# Sensor_LinearCCD_Socket.net
KiCad netlist of a schematic drawn in EAGLE
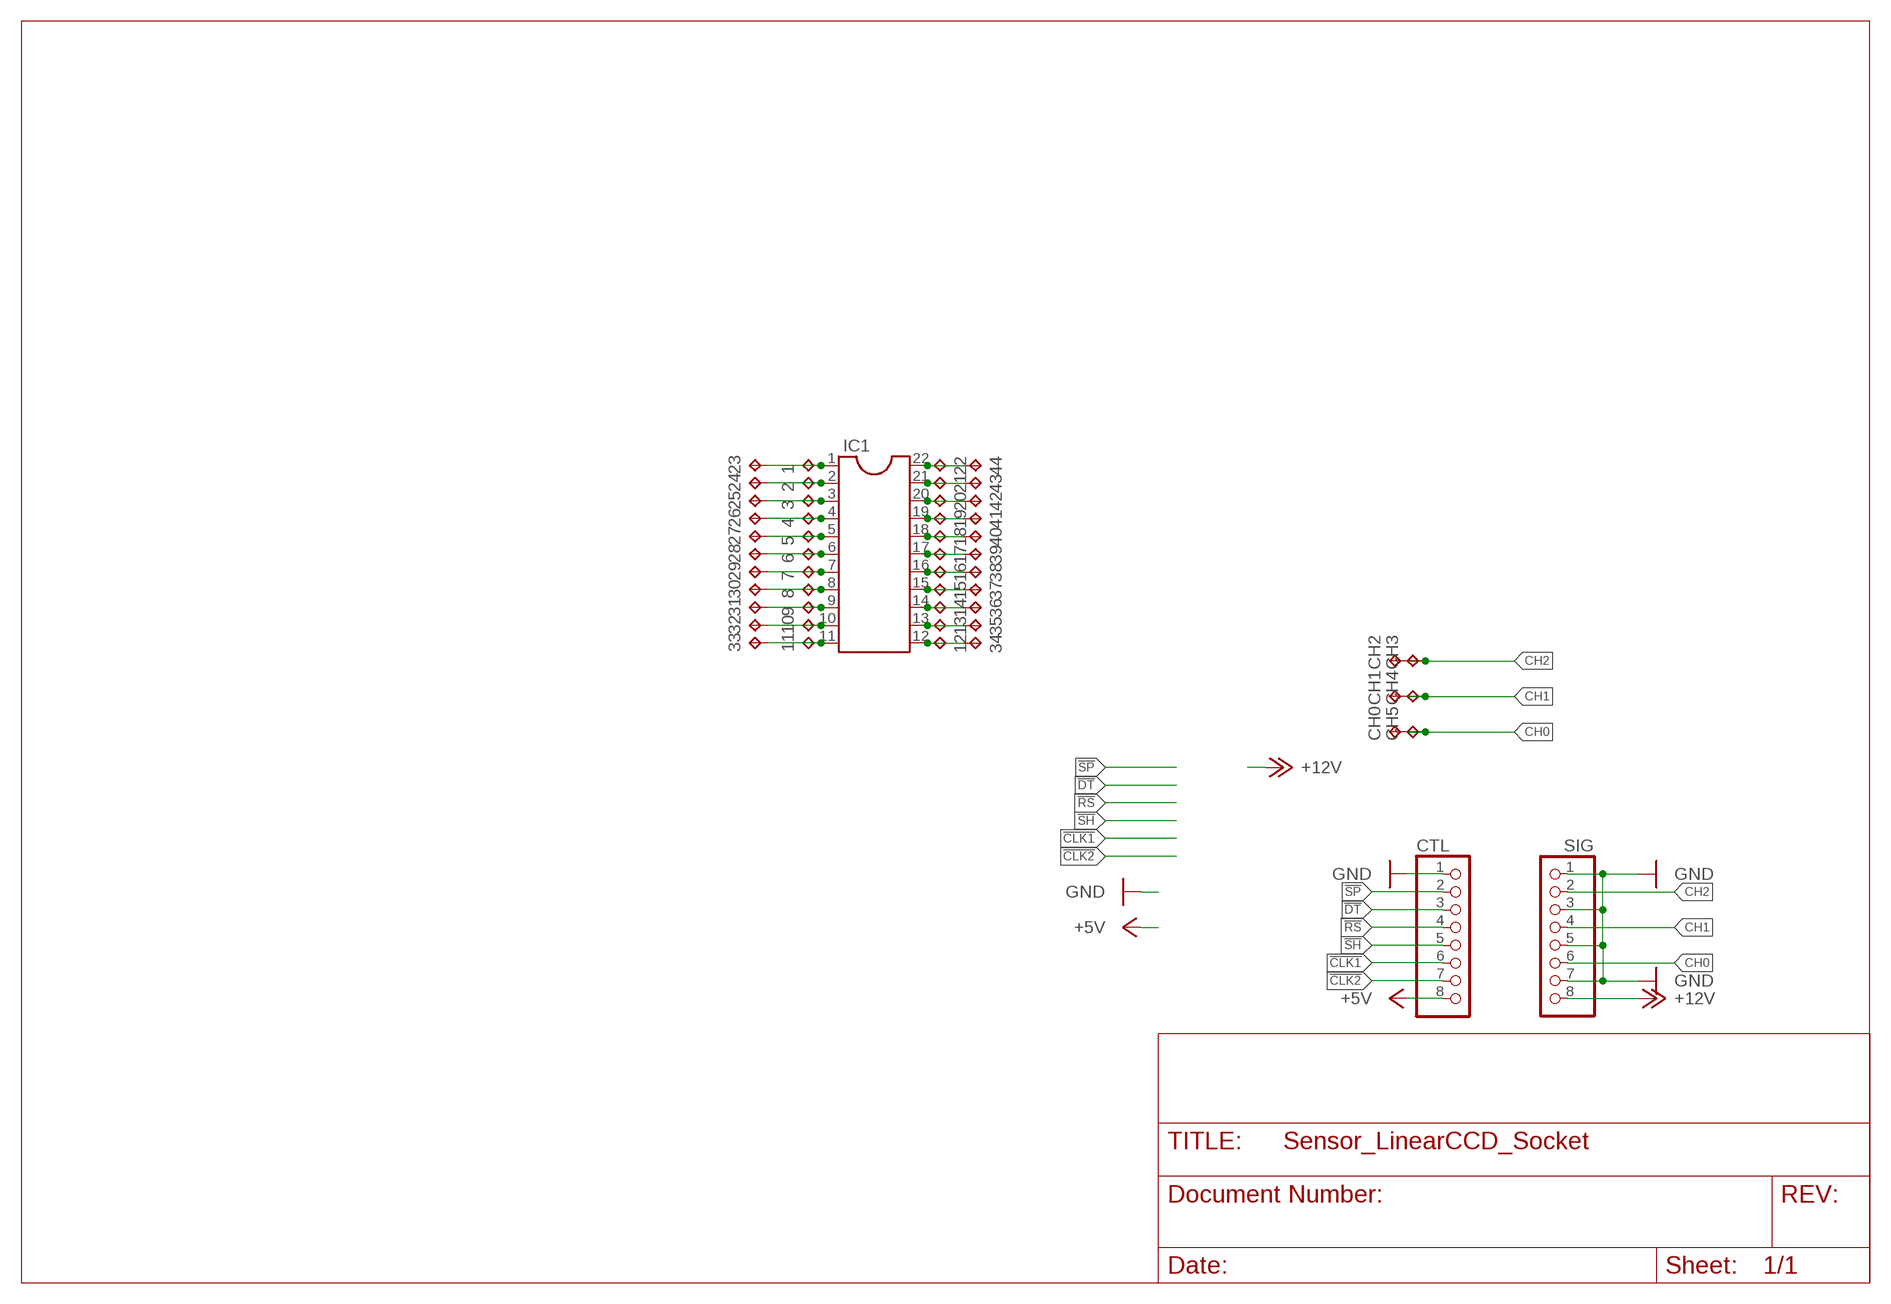
[diagram p0: schematic, sheet 1]

(export (version "E")
  (design (tool "Eeschema 10.0.6"))
  (components
    (comp (ref "1")
      (value "TPTP15SQ")
      (footprint "eagle-import:TP15SQ")
      (libsource (lib "eagle-import") (part "TPTP15SQ"))
    )
    (comp (ref "2")
      (value "TPTP15SQ")
      (footprint "eagle-import:TP15SQ")
      (libsource (lib "eagle-import") (part "TPTP15SQ"))
    )
    (comp (ref "3")
      (value "TPTP15SQ")
      (footprint "eagle-import:TP15SQ")
      (libsource (lib "eagle-import") (part "TPTP15SQ"))
    )
    (comp (ref "4")
      (value "TPTP15SQ")
      (footprint "eagle-import:TP15SQ")
      (libsource (lib "eagle-import") (part "TPTP15SQ"))
    )
    (comp (ref "5")
      (value "TPTP15SQ")
      (footprint "eagle-import:TP15SQ")
      (libsource (lib "eagle-import") (part "TPTP15SQ"))
    )
    (comp (ref "6")
      (value "TPTP15SQ")
      (footprint "eagle-import:TP15SQ")
      (libsource (lib "eagle-import") (part "TPTP15SQ"))
    )
    (comp (ref "7")
      (value "TPTP15SQ")
      (footprint "eagle-import:TP15SQ")
      (libsource (lib "eagle-import") (part "TPTP15SQ"))
    )
    (comp (ref "8")
      (value "TPTP15SQ")
      (footprint "eagle-import:TP15SQ")
      (libsource (lib "eagle-import") (part "TPTP15SQ"))
    )
    (comp (ref "9")
      (value "TPTP15SQ")
      (footprint "eagle-import:TP15SQ")
      (libsource (lib "eagle-import") (part "TPTP15SQ"))
    )
    (comp (ref "10")
      (value "TPTP15SQ")
      (footprint "eagle-import:TP15SQ")
      (libsource (lib "eagle-import") (part "TPTP15SQ"))
    )
    (comp (ref "11")
      (value "TPTP15SQ")
      (footprint "eagle-import:TP15SQ")
      (libsource (lib "eagle-import") (part "TPTP15SQ"))
    )
    (comp (ref "12")
      (value "TPTP15SQ")
      (footprint "eagle-import:TP15SQ")
      (libsource (lib "eagle-import") (part "TPTP15SQ"))
    )
    (comp (ref "13")
      (value "TPTP15SQ")
      (footprint "eagle-import:TP15SQ")
      (libsource (lib "eagle-import") (part "TPTP15SQ"))
    )
    (comp (ref "14")
      (value "TPTP15SQ")
      (footprint "eagle-import:TP15SQ")
      (libsource (lib "eagle-import") (part "TPTP15SQ"))
    )
    (comp (ref "15")
      (value "TPTP15SQ")
      (footprint "eagle-import:TP15SQ")
      (libsource (lib "eagle-import") (part "TPTP15SQ"))
    )
    (comp (ref "16")
      (value "TPTP15SQ")
      (footprint "eagle-import:TP15SQ")
      (libsource (lib "eagle-import") (part "TPTP15SQ"))
    )
    (comp (ref "17")
      (value "TPTP15SQ")
      (footprint "eagle-import:TP15SQ")
      (libsource (lib "eagle-import") (part "TPTP15SQ"))
    )
    (comp (ref "18")
      (value "TPTP15SQ")
      (footprint "eagle-import:TP15SQ")
      (libsource (lib "eagle-import") (part "TPTP15SQ"))
    )
    (comp (ref "19")
      (value "TPTP15SQ")
      (footprint "eagle-import:TP15SQ")
      (libsource (lib "eagle-import") (part "TPTP15SQ"))
    )
    (comp (ref "20")
      (value "TPTP15SQ")
      (footprint "eagle-import:TP15SQ")
      (libsource (lib "eagle-import") (part "TPTP15SQ"))
    )
    (comp (ref "21")
      (value "TPTP15SQ")
      (footprint "eagle-import:TP15SQ")
      (libsource (lib "eagle-import") (part "TPTP15SQ"))
    )
    (comp (ref "22")
      (value "TPTP15SQ")
      (footprint "eagle-import:TP15SQ")
      (libsource (lib "eagle-import") (part "TPTP15SQ"))
    )
    (comp (ref "23")
      (value "TPTP15SQ")
      (footprint "eagle-import:TP15SQ")
      (libsource (lib "eagle-import") (part "TPTP15SQ"))
    )
    (comp (ref "24")
      (value "TPTP15SQ")
      (footprint "eagle-import:TP15SQ")
      (libsource (lib "eagle-import") (part "TPTP15SQ"))
    )
    (comp (ref "25")
      (value "TPTP15SQ")
      (footprint "eagle-import:TP15SQ")
      (libsource (lib "eagle-import") (part "TPTP15SQ"))
    )
    (comp (ref "26")
      (value "TPTP15SQ")
      (footprint "eagle-import:TP15SQ")
      (libsource (lib "eagle-import") (part "TPTP15SQ"))
    )
    (comp (ref "27")
      (value "TPTP15SQ")
      (footprint "eagle-import:TP15SQ")
      (libsource (lib "eagle-import") (part "TPTP15SQ"))
    )
    (comp (ref "28")
      (value "TPTP15SQ")
      (footprint "eagle-import:TP15SQ")
      (libsource (lib "eagle-import") (part "TPTP15SQ"))
    )
    (comp (ref "29")
      (value "TPTP15SQ")
      (footprint "eagle-import:TP15SQ")
      (libsource (lib "eagle-import") (part "TPTP15SQ"))
    )
    (comp (ref "30")
      (value "TPTP15SQ")
      (footprint "eagle-import:TP15SQ")
      (libsource (lib "eagle-import") (part "TPTP15SQ"))
    )
    (comp (ref "31")
      (value "TPTP15SQ")
      (footprint "eagle-import:TP15SQ")
      (libsource (lib "eagle-import") (part "TPTP15SQ"))
    )
    (comp (ref "32")
      (value "TPTP15SQ")
      (footprint "eagle-import:TP15SQ")
      (libsource (lib "eagle-import") (part "TPTP15SQ"))
    )
    (comp (ref "33")
      (value "TPTP15SQ")
      (footprint "eagle-import:TP15SQ")
      (libsource (lib "eagle-import") (part "TPTP15SQ"))
    )
    (comp (ref "34")
      (value "TPTP15SQ")
      (footprint "eagle-import:TP15SQ")
      (libsource (lib "eagle-import") (part "TPTP15SQ"))
    )
    (comp (ref "35")
      (value "TPTP15SQ")
      (footprint "eagle-import:TP15SQ")
      (libsource (lib "eagle-import") (part "TPTP15SQ"))
    )
    (comp (ref "36")
      (value "TPTP15SQ")
      (footprint "eagle-import:TP15SQ")
      (libsource (lib "eagle-import") (part "TPTP15SQ"))
    )
    (comp (ref "37")
      (value "TPTP15SQ")
      (footprint "eagle-import:TP15SQ")
      (libsource (lib "eagle-import") (part "TPTP15SQ"))
    )
    (comp (ref "38")
      (value "TPTP15SQ")
      (footprint "eagle-import:TP15SQ")
      (libsource (lib "eagle-import") (part "TPTP15SQ"))
    )
    (comp (ref "39")
      (value "TPTP15SQ")
      (footprint "eagle-import:TP15SQ")
      (libsource (lib "eagle-import") (part "TPTP15SQ"))
    )
    (comp (ref "40")
      (value "TPTP15SQ")
      (footprint "eagle-import:TP15SQ")
      (libsource (lib "eagle-import") (part "TPTP15SQ"))
    )
    (comp (ref "41")
      (value "TPTP15SQ")
      (footprint "eagle-import:TP15SQ")
      (libsource (lib "eagle-import") (part "TPTP15SQ"))
    )
    (comp (ref "42")
      (value "TPTP15SQ")
      (footprint "eagle-import:TP15SQ")
      (libsource (lib "eagle-import") (part "TPTP15SQ"))
    )
    (comp (ref "43")
      (value "TPTP15SQ")
      (footprint "eagle-import:TP15SQ")
      (libsource (lib "eagle-import") (part "TPTP15SQ"))
    )
    (comp (ref "44")
      (value "TPTP15SQ")
      (footprint "eagle-import:TP15SQ")
      (libsource (lib "eagle-import") (part "TPTP15SQ"))
    )
    (comp (ref "CH0")
      (value "TPTP15SQ")
      (footprint "eagle-import:TP15SQ")
      (libsource (lib "eagle-import") (part "TPTP15SQ"))
    )
    (comp (ref "CH1")
      (value "TPTP15SQ")
      (footprint "eagle-import:TP15SQ")
      (libsource (lib "eagle-import") (part "TPTP15SQ"))
    )
    (comp (ref "CH2")
      (value "TPTP15SQ")
      (footprint "eagle-import:TP15SQ")
      (libsource (lib "eagle-import") (part "TPTP15SQ"))
    )
    (comp (ref "CH3")
      (value "TPTP15SQ")
      (footprint "eagle-import:TP15SQ")
      (libsource (lib "eagle-import") (part "TPTP15SQ"))
    )
    (comp (ref "CH4")
      (value "TPTP15SQ")
      (footprint "eagle-import:TP15SQ")
      (libsource (lib "eagle-import") (part "TPTP15SQ"))
    )
    (comp (ref "CH5")
      (value "TPTP15SQ")
      (footprint "eagle-import:TP15SQ")
      (libsource (lib "eagle-import") (part "TPTP15SQ"))
    )
    (comp (ref "CTL")
      (value "PINHD-1X8_2.00")
      (footprint "eagle-import:1X08M")
      (libsource (lib "eagle-import") (part "PINHD-1X8_2.00"))
    )
    (comp (ref "IC1")
      (value "DIL22-4")
      (footprint "eagle-import:DIL22-4")
      (libsource (lib "eagle-import") (part "DIL22-4"))
    )
    (comp (ref "SIG")
      (value "PINHD-1X8_2.00")
      (footprint "eagle-import:1X08M")
      (libsource (lib "eagle-import") (part "PINHD-1X8_2.00"))
    )
  )
  (nets
    (net (code "1") (name "+5V") (class "Default")
      (node (ref "CTL") (pin "8") (pinfunction "8_8") (pintype "passive"))
    )
    (net (code "2") (name "+12V") (class "Default")
      (node (ref "SIG") (pin "8") (pinfunction "8_8") (pintype "passive"))
    )
    (net (code "3") (name "/~{CLK1}") (class "Default")
      (node (ref "CTL") (pin "6") (pinfunction "6_6") (pintype "passive"))
    )
    (net (code "4") (name "/~{CLK2}") (class "Default")
      (node (ref "CTL") (pin "7") (pinfunction "7_7") (pintype "passive"))
    )
    (net (code "5") (name "/~{DT}") (class "Default")
      (node (ref "CTL") (pin "3") (pinfunction "3_3") (pintype "passive"))
    )
    (net (code "6") (name "/~{RS}") (class "Default")
      (node (ref "CTL") (pin "4") (pinfunction "4_4") (pintype "passive"))
    )
    (net (code "7") (name "/~{SH}") (class "Default")
      (node (ref "CTL") (pin "5") (pinfunction "5_5") (pintype "passive"))
    )
    (net (code "8") (name "/~{SP}") (class "Default")
      (node (ref "CTL") (pin "2") (pinfunction "2_2") (pintype "passive"))
    )
    (net (code "9") (name "CH0") (class "Default")
      (node (ref "CH0") (pin "TP") (pinfunction "TP_TP") (pintype "input"))
      (node (ref "CH5") (pin "TP") (pinfunction "TP_TP") (pintype "input"))
      (node (ref "SIG") (pin "6") (pinfunction "6_6") (pintype "passive"))
    )
    (net (code "10") (name "CH1") (class "Default")
      (node (ref "CH1") (pin "TP") (pinfunction "TP_TP") (pintype "input"))
      (node (ref "CH4") (pin "TP") (pinfunction "TP_TP") (pintype "input"))
      (node (ref "SIG") (pin "4") (pinfunction "4_4") (pintype "passive"))
    )
    (net (code "11") (name "CH2") (class "Default")
      (node (ref "CH2") (pin "TP") (pinfunction "TP_TP") (pintype "input"))
      (node (ref "CH3") (pin "TP") (pinfunction "TP_TP") (pintype "input"))
      (node (ref "SIG") (pin "2") (pinfunction "2_2") (pintype "passive"))
    )
    (net (code "12") (name "GND") (class "Default")
      (node (ref "CTL") (pin "1") (pinfunction "1_1") (pintype "passive"))
      (node (ref "SIG") (pin "1") (pinfunction "1_1") (pintype "passive"))
      (node (ref "SIG") (pin "3") (pinfunction "3_3") (pintype "passive"))
      (node (ref "SIG") (pin "5") (pinfunction "5_5") (pintype "passive"))
      (node (ref "SIG") (pin "7") (pinfunction "7_7") (pintype "passive"))
    )
    (net (code "13") (name "Net-(1-PadTP)") (class "Default")
      (node (ref "1") (pin "TP") (pinfunction "TP_TP") (pintype "input"))
      (node (ref "23") (pin "TP") (pinfunction "TP_TP") (pintype "input"))
      (node (ref "IC1") (pin "1") (pinfunction "1_1") (pintype "passive"))
    )
    (net (code "14") (name "Net-(2-PadTP)") (class "Default")
      (node (ref "2") (pin "TP") (pinfunction "TP_TP") (pintype "input"))
      (node (ref "24") (pin "TP") (pinfunction "TP_TP") (pintype "input"))
      (node (ref "IC1") (pin "2") (pinfunction "2_2") (pintype "passive"))
    )
    (net (code "15") (name "Net-(10-PadTP)") (class "Default")
      (node (ref "10") (pin "TP") (pinfunction "TP_TP") (pintype "input"))
      (node (ref "32") (pin "TP") (pinfunction "TP_TP") (pintype "input"))
      (node (ref "IC1") (pin "10") (pinfunction "10_10") (pintype "passive"))
    )
    (net (code "16") (name "Net-(11-PadTP)") (class "Default")
      (node (ref "11") (pin "TP") (pinfunction "TP_TP") (pintype "input"))
      (node (ref "33") (pin "TP") (pinfunction "TP_TP") (pintype "input"))
      (node (ref "IC1") (pin "11") (pinfunction "11_11") (pintype "passive"))
    )
    (net (code "17") (name "Net-(12-PadTP)") (class "Default")
      (node (ref "12") (pin "TP") (pinfunction "TP_TP") (pintype "input"))
      (node (ref "34") (pin "TP") (pinfunction "TP_TP") (pintype "input"))
      (node (ref "IC1") (pin "12") (pinfunction "12_12") (pintype "passive"))
    )
    (net (code "18") (name "Net-(13-PadTP)") (class "Default")
      (node (ref "13") (pin "TP") (pinfunction "TP_TP") (pintype "input"))
      (node (ref "35") (pin "TP") (pinfunction "TP_TP") (pintype "input"))
      (node (ref "IC1") (pin "13") (pinfunction "13_13") (pintype "passive"))
    )
    (net (code "19") (name "Net-(14-PadTP)") (class "Default")
      (node (ref "14") (pin "TP") (pinfunction "TP_TP") (pintype "input"))
      (node (ref "36") (pin "TP") (pinfunction "TP_TP") (pintype "input"))
      (node (ref "IC1") (pin "14") (pinfunction "14_14") (pintype "passive"))
    )
    (net (code "20") (name "Net-(15-PadTP)") (class "Default")
      (node (ref "15") (pin "TP") (pinfunction "TP_TP") (pintype "input"))
      (node (ref "37") (pin "TP") (pinfunction "TP_TP") (pintype "input"))
      (node (ref "IC1") (pin "15") (pinfunction "15_15") (pintype "passive"))
    )
    (net (code "21") (name "Net-(16-PadTP)") (class "Default")
      (node (ref "16") (pin "TP") (pinfunction "TP_TP") (pintype "input"))
      (node (ref "38") (pin "TP") (pinfunction "TP_TP") (pintype "input"))
      (node (ref "IC1") (pin "16") (pinfunction "16_16") (pintype "passive"))
    )
    (net (code "22") (name "Net-(17-PadTP)") (class "Default")
      (node (ref "17") (pin "TP") (pinfunction "TP_TP") (pintype "input"))
      (node (ref "39") (pin "TP") (pinfunction "TP_TP") (pintype "input"))
      (node (ref "IC1") (pin "17") (pinfunction "17_17") (pintype "passive"))
    )
    (net (code "23") (name "Net-(18-PadTP)") (class "Default")
      (node (ref "18") (pin "TP") (pinfunction "TP_TP") (pintype "input"))
      (node (ref "40") (pin "TP") (pinfunction "TP_TP") (pintype "input"))
      (node (ref "IC1") (pin "18") (pinfunction "18_18") (pintype "passive"))
    )
    (net (code "24") (name "Net-(19-PadTP)") (class "Default")
      (node (ref "19") (pin "TP") (pinfunction "TP_TP") (pintype "input"))
      (node (ref "41") (pin "TP") (pinfunction "TP_TP") (pintype "input"))
      (node (ref "IC1") (pin "19") (pinfunction "19_19") (pintype "passive"))
    )
    (net (code "25") (name "Net-(20-PadTP)") (class "Default")
      (node (ref "20") (pin "TP") (pinfunction "TP_TP") (pintype "input"))
      (node (ref "42") (pin "TP") (pinfunction "TP_TP") (pintype "input"))
      (node (ref "IC1") (pin "20") (pinfunction "20_20") (pintype "passive"))
    )
    (net (code "26") (name "Net-(21-PadTP)") (class "Default")
      (node (ref "21") (pin "TP") (pinfunction "TP_TP") (pintype "input"))
      (node (ref "43") (pin "TP") (pinfunction "TP_TP") (pintype "input"))
      (node (ref "IC1") (pin "21") (pinfunction "21_21") (pintype "passive"))
    )
    (net (code "27") (name "Net-(22-PadTP)") (class "Default")
      (node (ref "22") (pin "TP") (pinfunction "TP_TP") (pintype "input"))
      (node (ref "44") (pin "TP") (pinfunction "TP_TP") (pintype "input"))
      (node (ref "IC1") (pin "22") (pinfunction "22_22") (pintype "passive"))
    )
    (net (code "28") (name "Net-(25-PadTP)") (class "Default")
      (node (ref "25") (pin "TP") (pinfunction "TP_TP") (pintype "input"))
      (node (ref "3") (pin "TP") (pinfunction "TP_TP") (pintype "input"))
      (node (ref "IC1") (pin "3") (pinfunction "3_3") (pintype "passive"))
    )
    (net (code "29") (name "Net-(26-PadTP)") (class "Default")
      (node (ref "26") (pin "TP") (pinfunction "TP_TP") (pintype "input"))
      (node (ref "4") (pin "TP") (pinfunction "TP_TP") (pintype "input"))
      (node (ref "IC1") (pin "4") (pinfunction "4_4") (pintype "passive"))
    )
    (net (code "30") (name "Net-(27-PadTP)") (class "Default")
      (node (ref "27") (pin "TP") (pinfunction "TP_TP") (pintype "input"))
      (node (ref "5") (pin "TP") (pinfunction "TP_TP") (pintype "input"))
      (node (ref "IC1") (pin "5") (pinfunction "5_5") (pintype "passive"))
    )
    (net (code "31") (name "Net-(28-PadTP)") (class "Default")
      (node (ref "28") (pin "TP") (pinfunction "TP_TP") (pintype "input"))
      (node (ref "6") (pin "TP") (pinfunction "TP_TP") (pintype "input"))
      (node (ref "IC1") (pin "6") (pinfunction "6_6") (pintype "passive"))
    )
    (net (code "32") (name "Net-(29-PadTP)") (class "Default")
      (node (ref "29") (pin "TP") (pinfunction "TP_TP") (pintype "input"))
      (node (ref "7") (pin "TP") (pinfunction "TP_TP") (pintype "input"))
      (node (ref "IC1") (pin "7") (pinfunction "7_7") (pintype "passive"))
    )
    (net (code "33") (name "Net-(30-PadTP)") (class "Default")
      (node (ref "30") (pin "TP") (pinfunction "TP_TP") (pintype "input"))
      (node (ref "8") (pin "TP") (pinfunction "TP_TP") (pintype "input"))
      (node (ref "IC1") (pin "8") (pinfunction "8_8") (pintype "passive"))
    )
    (net (code "34") (name "Net-(31-PadTP)") (class "Default")
      (node (ref "31") (pin "TP") (pinfunction "TP_TP") (pintype "input"))
      (node (ref "9") (pin "TP") (pinfunction "TP_TP") (pintype "input"))
      (node (ref "IC1") (pin "9") (pinfunction "9_9") (pintype "passive"))
    )
  )
)
